# 5_gate_driver.net
KiCad netlist of a schematic drawn in Altium Designer
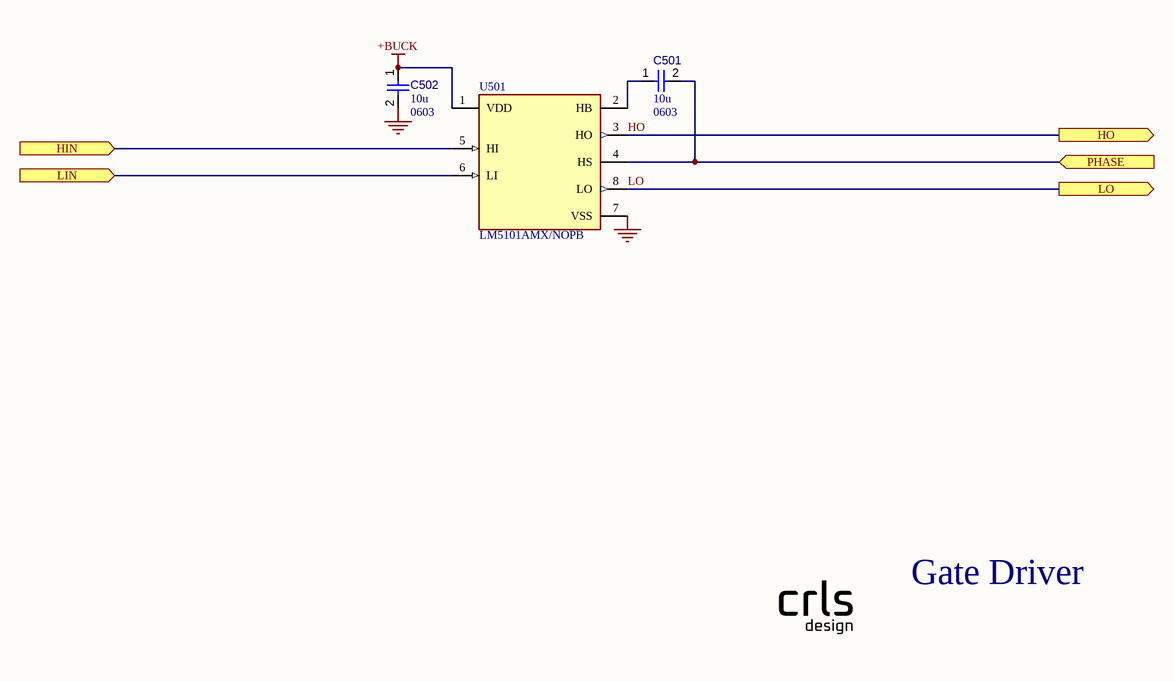
[diagram p0: 5 gate driver.SchDoc]

(export (version "E")
  (design (tool "Eeschema 10.0.6"))
  (components
    (comp (ref "C501")
      (value "10u")
      (footprint "CAPC0603(1608)100_L")
      (description "Capacitor")
      (fields
        (field (name "CASE/PACKAGE") "0603")
        (field (name "TOLERANCE") "20%")
        (field (name "Comment") "Capacitors,ceramic,0603,20%,10u,25V")
      )
      (libsource (lib "UBC Uncrewed Aircraft Systems") (part "CAP-NP-2"))
    )
    (comp (ref "C502")
      (value "10u")
      (footprint "CAPC0603(1608)100_L")
      (description "Capacitor")
      (fields
        (field (name "CASE/PACKAGE") "0603")
        (field (name "TOLERANCE") "20%")
        (field (name "Comment") "Capacitors,ceramic,0603,20%,10u,25V")
      )
      (libsource (lib "UBC Uncrewed Aircraft Systems") (part "CAP-NP-2"))
    )
    (comp (ref "U501")
      (value "LM5101AMX/NOPB")
      (footprint "FP-D0008A-MFG")
      (description "IC GATE DRVR HALF-BRIDGE 8SOIC")
      (libsource (lib "Altium Content Vault") (part "cccb75fdea50f8568ff7d6a99a5b102"))
    )
  )
  (nets
    (net (code "1") (name "+BUCK") (class "Default")
      (node (ref "C502") (pin "1") (pinfunction "1_1") (pintype "passive"))
      (node (ref "U501") (pin "1") (pinfunction "VDD_1") (pintype "power_in"))
    )
    (net (code "2") (name "/HIN") (class "Default")
      (node (ref "U501") (pin "5") (pinfunction "HI_5") (pintype "input"))
    )
    (net (code "3") (name "/HO") (class "Default")
      (node (ref "U501") (pin "3") (pinfunction "HO_3") (pintype "output"))
    )
    (net (code "4") (name "/LIN") (class "Default")
      (node (ref "U501") (pin "6") (pinfunction "LI_6") (pintype "input"))
    )
    (net (code "5") (name "/LO") (class "Default")
      (node (ref "U501") (pin "8") (pinfunction "LO_8") (pintype "output"))
    )
    (net (code "6") (name "/PHASE") (class "Default")
      (node (ref "C501") (pin "2") (pinfunction "2_2") (pintype "passive"))
      (node (ref "U501") (pin "4") (pinfunction "HS_4") (pintype "passive"))
    )
    (net (code "7") (name "GND") (class "Default")
      (node (ref "C502") (pin "2") (pinfunction "2_2") (pintype "passive"))
      (node (ref "U501") (pin "7") (pinfunction "VSS_7") (pintype "power_in"))
    )
    (net (code "8") (name "Net-(U501-HB)") (class "Default")
      (node (ref "C501") (pin "1") (pinfunction "1_1") (pintype "passive"))
      (node (ref "U501") (pin "2") (pinfunction "HB_2") (pintype "power_in"))
    )
  )
)
